# AD5940PSTAT.net
KiCad netlist of a schematic drawn in Altium Designer
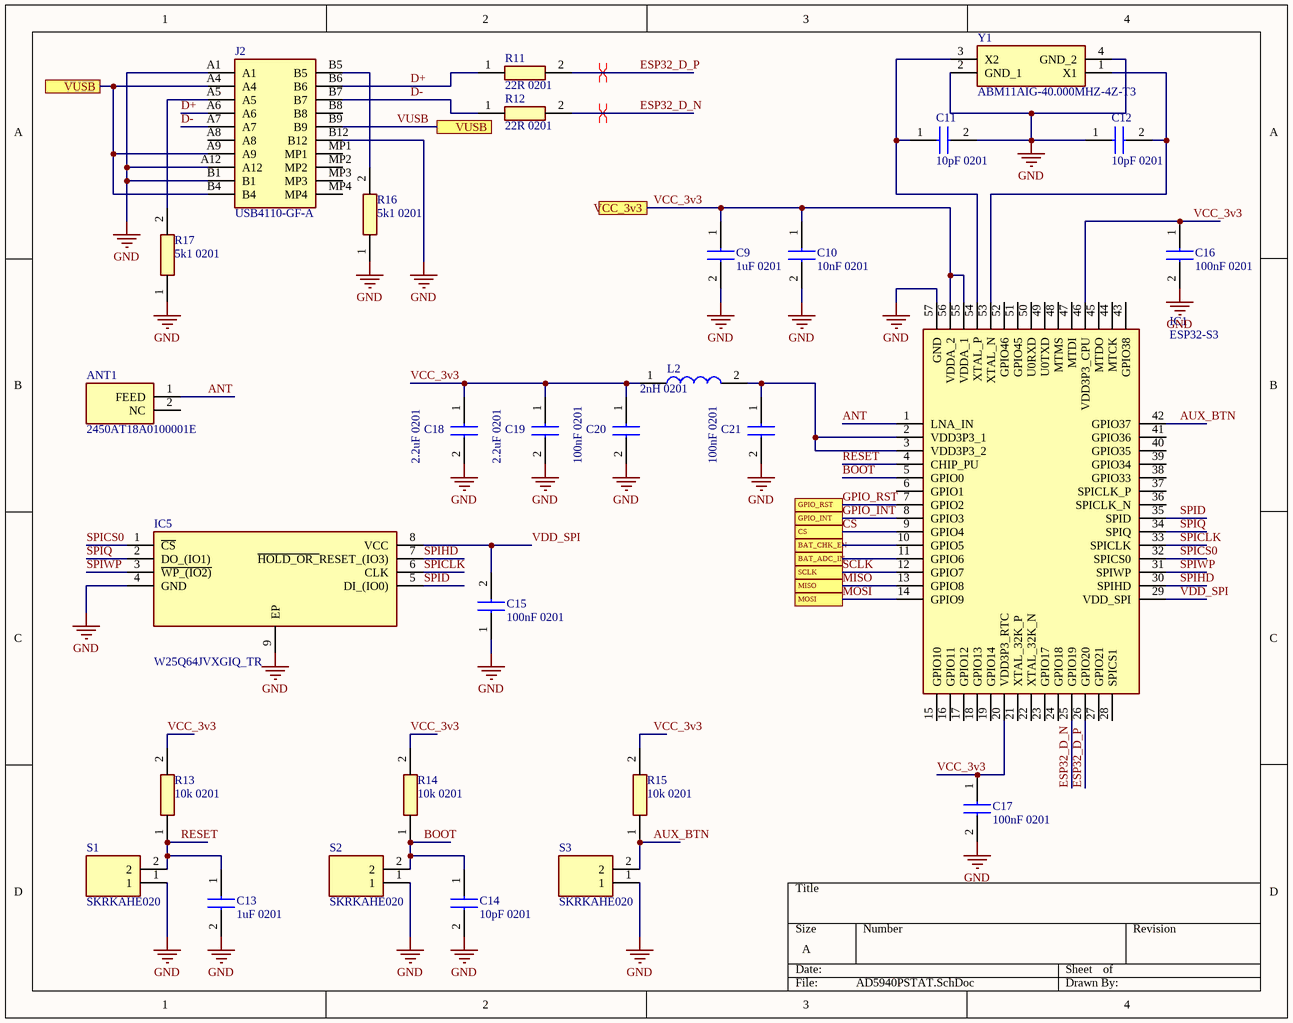
[diagram p0: AD5940PSTAT.SchDoc]

(export (version "E")
  (design (tool "Eeschema 10.0.6"))
  (components
    (comp (ref "ANT1")
      (value "2450AT18A0100001E")
      (footprint "SamacSys:2450AT18A0100001E")
      (description "Antenna")
      (libsource (lib "*") (part "2450AT18A0100001E"))
    )
    (comp (ref "C9")
      (value "1uF 0201")
      (footprint "SamacSys:CAPC0603X33N")
      (description "Capacitor")
      (fields
        (field (name "MANUFACTURER_PART_NUMBER") "02013A0R5BAT2A")
        (field (name "MOUSER PART NUMBER") "581-02013A0R5BAT2A")
      )
      (libsource (lib "*") (part "02013A0R5BAT2A"))
    )
    (comp (ref "C10")
      (value "10nF 0201")
      (footprint "SamacSys:CAPC0603X33N")
      (description "Capacitor")
      (fields
        (field (name "MANUFACTURER_PART_NUMBER") "02013A0R5BAT2A")
        (field (name "MOUSER PART NUMBER") "581-02013A0R5BAT2A")
      )
      (libsource (lib "*") (part "02013A0R5BAT2A"))
    )
    (comp (ref "C11")
      (value "10pF 0201")
      (footprint "SamacSys:CAPC0603X33N")
      (description "Capacitor")
      (fields
        (field (name "MANUFACTURER_PART_NUMBER") "02013A0R5BAT2A")
        (field (name "MOUSER PART NUMBER") "581-02013A0R5BAT2A")
      )
      (libsource (lib "*") (part "02013A0R5BAT2A"))
    )
    (comp (ref "C12")
      (value "10pF 0201")
      (footprint "SamacSys:CAPC0603X33N")
      (description "Capacitor")
      (fields
        (field (name "MANUFACTURER_PART_NUMBER") "02013A0R5BAT2A")
        (field (name "MOUSER PART NUMBER") "581-02013A0R5BAT2A")
      )
      (libsource (lib "*") (part "02013A0R5BAT2A"))
    )
    (comp (ref "C13")
      (value "1uF 0201")
      (footprint "SamacSys:CAPC0603X33N")
      (description "Capacitor")
      (fields
        (field (name "MANUFACTURER_PART_NUMBER") "02013A0R5BAT2A")
        (field (name "MOUSER PART NUMBER") "581-02013A0R5BAT2A")
      )
      (libsource (lib "*") (part "02013A0R5BAT2A"))
    )
    (comp (ref "C14")
      (value "10pF 0201")
      (footprint "SamacSys:CAPC0603X33N")
      (description "Capacitor")
      (fields
        (field (name "MANUFACTURER_PART_NUMBER") "02013A0R5BAT2A")
        (field (name "MOUSER PART NUMBER") "581-02013A0R5BAT2A")
      )
      (libsource (lib "*") (part "02013A0R5BAT2A"))
    )
    (comp (ref "C15")
      (value "100nF 0201")
      (footprint "SamacSys:CAPC0603X33N")
      (description "Capacitor")
      (fields
        (field (name "MANUFACTURER_PART_NUMBER") "02013A0R5BAT2A")
        (field (name "MOUSER PART NUMBER") "581-02013A0R5BAT2A")
      )
      (libsource (lib "*") (part "02013A0R5BAT2A"))
    )
    (comp (ref "C16")
      (value "100nF 0201")
      (footprint "SamacSys:CAPC0603X33N")
      (description "Capacitor")
      (fields
        (field (name "MANUFACTURER_PART_NUMBER") "02013A0R5BAT2A")
        (field (name "MOUSER PART NUMBER") "581-02013A0R5BAT2A")
      )
      (libsource (lib "*") (part "02013A0R5BAT2A"))
    )
    (comp (ref "C17")
      (value "100nF 0201")
      (footprint "SamacSys:CAPC0603X33N")
      (description "Capacitor")
      (fields
        (field (name "MANUFACTURER_PART_NUMBER") "02013A0R5BAT2A")
        (field (name "MOUSER PART NUMBER") "581-02013A0R5BAT2A")
      )
      (libsource (lib "*") (part "02013A0R5BAT2A"))
    )
    (comp (ref "C18")
      (value "2.2uF 0201")
      (footprint "SamacSys:CAPC0603X33N")
      (description "Capacitor")
      (fields
        (field (name "MANUFACTURER_PART_NUMBER") "02013A0R5BAT2A")
        (field (name "MOUSER PART NUMBER") "581-02013A0R5BAT2A")
      )
      (libsource (lib "*") (part "02013A0R5BAT2A"))
    )
    (comp (ref "C19")
      (value "2.2uF 0201")
      (footprint "SamacSys:CAPC0603X33N")
      (description "Capacitor")
      (fields
        (field (name "MANUFACTURER_PART_NUMBER") "02013A0R5BAT2A")
        (field (name "MOUSER PART NUMBER") "581-02013A0R5BAT2A")
      )
      (libsource (lib "*") (part "02013A0R5BAT2A"))
    )
    (comp (ref "C20")
      (value "100nF 0201")
      (footprint "SamacSys:CAPC0603X33N")
      (description "Capacitor")
      (fields
        (field (name "MANUFACTURER_PART_NUMBER") "02013A0R5BAT2A")
        (field (name "MOUSER PART NUMBER") "581-02013A0R5BAT2A")
      )
      (libsource (lib "*") (part "02013A0R5BAT2A"))
    )
    (comp (ref "C21")
      (value "100nF 0201")
      (footprint "SamacSys:CAPC0603X33N")
      (description "Capacitor")
      (fields
        (field (name "MANUFACTURER_PART_NUMBER") "02013A0R5BAT2A")
        (field (name "MOUSER PART NUMBER") "581-02013A0R5BAT2A")
      )
      (libsource (lib "*") (part "02013A0R5BAT2A"))
    )
    (comp (ref "IC1")
      (value "ESP32-S3")
      (footprint "SamacSys:QFN40P700X700X90-57N-D")
      (description "Integrated Circuit")
      (fields (field (name "MOUSER PART NUMBER") "356-ESP32-S3"))
      (libsource (lib "SamacSys") (part "ESP32-S3"))
    )
    (comp (ref "IC5")
      (value "W25Q64JVXGIQ_TR")
      (footprint "SamacSys:SON80P400X400X50-9N")
      (description "Integrated Circuit")
      (fields
        (field (name "MANUFACTURER_PART_NUMBER") "W25Q64JVXGIQ TR")
        (field (name "MOUSER PART NUMBER") "454-W25Q64JVXGIQTR")
      )
      (libsource (lib "*") (part "W25Q64JVXGIQ_TR"))
    )
    (comp (ref "J2")
      (value "USB4110-GF-A")
      (footprint "SamacSys:USB4110GFA")
      (description "Connector")
      (fields (field (name "MOUSER PART NUMBER") "640-USB4110-GF-A"))
      (libsource (lib "*") (part "USB4110-GF-A"))
    )
    (comp (ref "L2")
      (value "2nH 0201")
      (footprint "SamacSys:LQP03TG3N1B02D")
      (description "Inductor")
      (fields
        (field (name "MANUFACTURER_PART_NUMBER") "LQP03TN2N0C02D")
        (field (name "MOUSER PART NUMBER") "81-LQP03TN2N0C02D")
      )
      (libsource (lib "*") (part "LQP03TN2N0C02D"))
    )
    (comp (ref "R11")
      (value "22R 0201")
      (footprint "SamacSys:RESC0603X28N")
      (description "Resistor")
      (fields (field (name "MANUFACTURER_PART_NUMBER") "CPF0201D422RE1"))
      (libsource (lib "") (part "CPF0201D422RE1_1"))
    )
    (comp (ref "R12")
      (value "22R 0201")
      (footprint "SamacSys:RESC0603X28N")
      (description "Resistor")
      (fields (field (name "MANUFACTURER_PART_NUMBER") "CPF0201D422RE1"))
      (libsource (lib "") (part "CPF0201D422RE1_1"))
    )
    (comp (ref "R13")
      (value "10k 0201")
      (footprint "SamacSys:RESC0603X28N")
      (description "Resistor")
      (fields (field (name "MANUFACTURER_PART_NUMBER") "CPF0201D422RE1"))
      (libsource (lib "*") (part "CPF0201D422RE1"))
    )
    (comp (ref "R14")
      (value "10k 0201")
      (footprint "SamacSys:RESC0603X28N")
      (description "Resistor")
      (fields (field (name "MANUFACTURER_PART_NUMBER") "CPF0201D422RE1"))
      (libsource (lib "*") (part "CPF0201D422RE1"))
    )
    (comp (ref "R15")
      (value "10k 0201")
      (footprint "SamacSys:RESC0603X28N")
      (description "Resistor")
      (fields (field (name "MANUFACTURER_PART_NUMBER") "CPF0201D422RE1"))
      (libsource (lib "*") (part "CPF0201D422RE1"))
    )
    (comp (ref "R16")
      (value "5k1 0201")
      (footprint "SamacSys:RESC0603X28N")
      (description "Resistor")
      (fields (field (name "MANUFACTURER_PART_NUMBER") "CPF0201D422RE1"))
      (libsource (lib "*") (part "CPF0201D422RE1"))
    )
    (comp (ref "R17")
      (value "5k1 0201")
      (footprint "SamacSys:RESC0603X28N")
      (description "Resistor")
      (fields (field (name "MANUFACTURER_PART_NUMBER") "CPF0201D422RE1"))
      (libsource (lib "*") (part "CPF0201D422RE1"))
    )
    (comp (ref "S1")
      (value "SKRKAHE020")
      (footprint "SamacSys:SKRKAEE020")
      (description "Switch")
      (fields (field (name "MOUSER PART NUMBER") "688-SKRKAHE010"))
      (libsource (lib "*") (part "SKRKAHE020"))
    )
    (comp (ref "S2")
      (value "SKRKAHE020")
      (footprint "SamacSys:SKRKAEE020")
      (description "Switch")
      (fields (field (name "MOUSER PART NUMBER") "688-SKRKAHE010"))
      (libsource (lib "*") (part "SKRKAHE020"))
    )
    (comp (ref "S3")
      (value "SKRKAHE020")
      (footprint "SamacSys:SKRKAEE020")
      (description "Switch")
      (fields (field (name "MOUSER PART NUMBER") "688-SKRKAHE010"))
      (libsource (lib "*") (part "SKRKAHE020"))
    )
    (comp (ref "Y1")
      (value "ABM11AIG-40.000MHZ-4Z-T3")
      (footprint "SamacSys:ABM11AIG16000MHZ81ZT")
      (description "Crystal or Oscillator")
      (fields (field (name "MOUSER PART NUMBER") "815-M11AIG-40-4ZT3"))
      (libsource (lib "*") (part "ABM11AIG-40.000MHZ-4Z-T3"))
    )
  )
  (nets
    (net (code "1") (name "/ANT") (class "Default")
      (node (ref "ANT1") (pin "1") (pinfunction "FEED_1") (pintype "passive"))
      (node (ref "IC1") (pin "1") (pinfunction "LNA_IN_1") (pintype "passive"))
    )
    (net (code "2") (name "/AUX_BTN") (class "Default")
      (node (ref "IC1") (pin "42") (pinfunction "GPIO37_42") (pintype "passive"))
      (node (ref "R15") (pin "1") (pinfunction "1_1") (pintype "passive"))
      (node (ref "S3") (pin "2") (pinfunction "2_2") (pintype "passive"))
    )
    (net (code "3") (name "/BAT_ADC_IN") (class "Default")
      (node (ref "IC1") (pin "11") (pinfunction "GPIO6_11") (pintype "passive"))
    )
    (net (code "4") (name "/BAT_CHK_EN") (class "Default")
      (node (ref "IC1") (pin "10") (pinfunction "GPIO5_10") (pintype "passive"))
    )
    (net (code "5") (name "/BOOT") (class "Default")
      (node (ref "C14") (pin "1") (pinfunction "1_1") (pintype "passive"))
      (node (ref "IC1") (pin "5") (pinfunction "GPIO0_5") (pintype "passive"))
      (node (ref "R14") (pin "1") (pinfunction "1_1") (pintype "passive"))
      (node (ref "S2") (pin "2") (pinfunction "2_2") (pintype "passive"))
    )
    (net (code "6") (name "/CS") (class "Default")
      (node (ref "IC1") (pin "9") (pinfunction "GPIO4_9") (pintype "passive"))
    )
    (net (code "7") (name "/D+") (class "Default")
      (node (ref "J2") (pin "A6") (pinfunction "A6_A6") (pintype "passive"))
      (node (ref "J2") (pin "B6") (pinfunction "B6_B6") (pintype "passive"))
      (node (ref "R11") (pin "1") (pinfunction "1_1") (pintype "passive"))
    )
    (net (code "8") (name "/D-") (class "Default")
      (node (ref "J2") (pin "A7") (pinfunction "A7_A7") (pintype "passive"))
      (node (ref "J2") (pin "B7") (pinfunction "B7_B7") (pintype "passive"))
      (node (ref "R12") (pin "1") (pinfunction "1_1") (pintype "passive"))
    )
    (net (code "9") (name "/ESP32_D_N") (class "Default")
      (node (ref "IC1") (pin "25") (pinfunction "GPIO19_25") (pintype "passive"))
      (node (ref "R12") (pin "2") (pinfunction "2_2") (pintype "passive"))
    )
    (net (code "10") (name "/ESP32_D_P") (class "Default")
      (node (ref "IC1") (pin "26") (pinfunction "GPIO20_26") (pintype "passive"))
      (node (ref "R11") (pin "2") (pinfunction "2_2") (pintype "passive"))
    )
    (net (code "11") (name "/GPIO_INT") (class "Default")
      (node (ref "IC1") (pin "8") (pinfunction "GPIO3_8") (pintype "passive"))
    )
    (net (code "12") (name "/GPIO_RST") (class "Default")
      (node (ref "IC1") (pin "7") (pinfunction "GPIO2_7") (pintype "passive"))
    )
    (net (code "13") (name "/MISO") (class "Default")
      (node (ref "IC1") (pin "13") (pinfunction "GPIO8_13") (pintype "passive"))
    )
    (net (code "14") (name "/MOSI") (class "Default")
      (node (ref "IC1") (pin "14") (pinfunction "GPIO9_14") (pintype "passive"))
    )
    (net (code "15") (name "/RESET") (class "Default")
      (node (ref "C13") (pin "1") (pinfunction "1_1") (pintype "passive"))
      (node (ref "IC1") (pin "4") (pinfunction "CHIP_PU_4") (pintype "passive"))
      (node (ref "R13") (pin "1") (pinfunction "1_1") (pintype "passive"))
      (node (ref "S1") (pin "2") (pinfunction "2_2") (pintype "passive"))
    )
    (net (code "16") (name "/SCLK") (class "Default")
      (node (ref "IC1") (pin "12") (pinfunction "GPIO7_12") (pintype "passive"))
    )
    (net (code "17") (name "/SPICLK") (class "Default")
      (node (ref "IC1") (pin "33") (pinfunction "SPICLK_33") (pintype "passive"))
      (node (ref "IC5") (pin "6") (pinfunction "CLK_6") (pintype "passive"))
    )
    (net (code "18") (name "/SPICS0") (class "Default")
      (node (ref "IC1") (pin "32") (pinfunction "SPICS0_32") (pintype "passive"))
      (node (ref "IC5") (pin "1") (pinfunction "~{CS}_1") (pintype "passive"))
    )
    (net (code "19") (name "/SPID") (class "Default")
      (node (ref "IC1") (pin "35") (pinfunction "SPID_35") (pintype "passive"))
      (node (ref "IC5") (pin "5") (pinfunction "DI_(IO0)_5") (pintype "passive"))
    )
    (net (code "20") (name "/SPIHD") (class "Default")
      (node (ref "IC1") (pin "30") (pinfunction "SPIHD_30") (pintype "passive"))
      (node (ref "IC5") (pin "7") (pinfunction "~{HOLD_OR_}RESET_(IO3)_7") (pintype "passive"))
    )
    (net (code "21") (name "/SPIQ") (class "Default")
      (node (ref "IC1") (pin "34") (pinfunction "SPIQ_34") (pintype "passive"))
      (node (ref "IC5") (pin "2") (pinfunction "DO_(IO1)_2") (pintype "passive"))
    )
    (net (code "22") (name "/SPIWP") (class "Default")
      (node (ref "IC1") (pin "31") (pinfunction "SPIWP_31") (pintype "passive"))
      (node (ref "IC5") (pin "3") (pinfunction "~{WP_(IO2)}_3") (pintype "passive"))
    )
    (net (code "23") (name "/VCC_3v3") (class "Default")
      (node (ref "C10") (pin "1") (pinfunction "1_1") (pintype "passive"))
      (node (ref "C16") (pin "1") (pinfunction "1_1") (pintype "passive"))
      (node (ref "C17") (pin "1") (pinfunction "1_1") (pintype "passive"))
      (node (ref "C18") (pin "1") (pinfunction "1_1") (pintype "passive"))
      (node (ref "C19") (pin "1") (pinfunction "1_1") (pintype "passive"))
      (node (ref "C20") (pin "1") (pinfunction "1_1") (pintype "passive"))
      (node (ref "C9") (pin "1") (pinfunction "1_1") (pintype "passive"))
      (node (ref "IC1") (pin "20") (pinfunction "VDD3P3_RTC_20") (pintype "passive"))
      (node (ref "IC1") (pin "46") (pinfunction "VDD3P3_CPU_46") (pintype "passive"))
      (node (ref "IC1") (pin "55") (pinfunction "VDDA_1_55") (pintype "passive"))
      (node (ref "IC1") (pin "56") (pinfunction "VDDA_2_56") (pintype "passive"))
      (node (ref "L2") (pin "1") (pinfunction "1_1") (pintype "passive"))
      (node (ref "R13") (pin "2") (pinfunction "2_2") (pintype "passive"))
      (node (ref "R14") (pin "2") (pinfunction "2_2") (pintype "passive"))
      (node (ref "R15") (pin "2") (pinfunction "2_2") (pintype "passive"))
    )
    (net (code "24") (name "/VDD_SPI") (class "Default")
      (node (ref "C15") (pin "2") (pinfunction "2_2") (pintype "passive"))
      (node (ref "IC1") (pin "29") (pinfunction "VDD_SPI_29") (pintype "passive"))
      (node (ref "IC5") (pin "8") (pinfunction "VCC_8") (pintype "passive"))
    )
    (net (code "25") (name "/VUSB") (class "Default")
      (node (ref "J2") (pin "A4") (pinfunction "A4_A4") (pintype "passive"))
      (node (ref "J2") (pin "A9") (pinfunction "A9_A9") (pintype "passive"))
      (node (ref "J2") (pin "B4") (pinfunction "B4_B4") (pintype "passive"))
      (node (ref "J2") (pin "B9") (pinfunction "B9_B9") (pintype "passive"))
    )
    (net (code "26") (name "GND") (class "Default")
      (node (ref "C10") (pin "2") (pinfunction "2_2") (pintype "passive"))
      (node (ref "C11") (pin "2") (pinfunction "2_2") (pintype "passive"))
      (node (ref "C12") (pin "1") (pinfunction "1_1") (pintype "passive"))
      (node (ref "C13") (pin "2") (pinfunction "2_2") (pintype "passive"))
      (node (ref "C14") (pin "2") (pinfunction "2_2") (pintype "passive"))
      (node (ref "C15") (pin "1") (pinfunction "1_1") (pintype "passive"))
      (node (ref "C16") (pin "2") (pinfunction "2_2") (pintype "passive"))
      (node (ref "C17") (pin "2") (pinfunction "2_2") (pintype "passive"))
      (node (ref "C18") (pin "2") (pinfunction "2_2") (pintype "passive"))
      (node (ref "C19") (pin "2") (pinfunction "2_2") (pintype "passive"))
      (node (ref "C20") (pin "2") (pinfunction "2_2") (pintype "passive"))
      (node (ref "C21") (pin "2") (pinfunction "2_2") (pintype "passive"))
      (node (ref "C9") (pin "2") (pinfunction "2_2") (pintype "passive"))
      (node (ref "IC1") (pin "57") (pinfunction "GND_57") (pintype "passive"))
      (node (ref "IC5") (pin "4") (pinfunction "GND_4") (pintype "passive"))
      (node (ref "IC5") (pin "9") (pinfunction "EP_9") (pintype "passive"))
      (node (ref "J2") (pin "A1") (pinfunction "A1_A1") (pintype "passive"))
      (node (ref "J2") (pin "A12") (pinfunction "A12_A12") (pintype "passive"))
      (node (ref "J2") (pin "B1") (pinfunction "B1_B1") (pintype "passive"))
      (node (ref "J2") (pin "B12") (pinfunction "B12_B12") (pintype "passive"))
      (node (ref "R16") (pin "1") (pinfunction "1_1") (pintype "passive"))
      (node (ref "R17") (pin "1") (pinfunction "1_1") (pintype "passive"))
      (node (ref "S1") (pin "1") (pinfunction "1_1") (pintype "passive"))
      (node (ref "S2") (pin "1") (pinfunction "1_1") (pintype "passive"))
      (node (ref "S3") (pin "1") (pinfunction "1_1") (pintype "passive"))
      (node (ref "Y1") (pin "2") (pinfunction "GND_1_2") (pintype "passive"))
      (node (ref "Y1") (pin "4") (pinfunction "GND_2_4") (pintype "passive"))
    )
    (net (code "27") (name "Net-(IC1-VDD3P3_1)") (class "Default")
      (node (ref "C21") (pin "1") (pinfunction "1_1") (pintype "passive"))
      (node (ref "IC1") (pin "2") (pinfunction "VDD3P3_1_2") (pintype "passive"))
      (node (ref "IC1") (pin "3") (pinfunction "VDD3P3_2_3") (pintype "passive"))
      (node (ref "L2") (pin "2") (pinfunction "2_2") (pintype "passive"))
    )
    (net (code "28") (name "Net-(IC1-XTAL_N)") (class "Default")
      (node (ref "C12") (pin "2") (pinfunction "2_2") (pintype "passive"))
      (node (ref "IC1") (pin "53") (pinfunction "XTAL_N_53") (pintype "passive"))
      (node (ref "Y1") (pin "1") (pinfunction "X1_1") (pintype "passive"))
    )
    (net (code "29") (name "Net-(IC1-XTAL_P)") (class "Default")
      (node (ref "C11") (pin "1") (pinfunction "1_1") (pintype "passive"))
      (node (ref "IC1") (pin "54") (pinfunction "XTAL_P_54") (pintype "passive"))
      (node (ref "Y1") (pin "3") (pinfunction "X2_3") (pintype "passive"))
    )
    (net (code "30") (name "Net-(J2-PadA5)") (class "Default")
      (node (ref "J2") (pin "A5") (pinfunction "A5_A5") (pintype "passive"))
      (node (ref "R17") (pin "2") (pinfunction "2_2") (pintype "passive"))
    )
    (net (code "31") (name "Net-(J2-PadB5)") (class "Default")
      (node (ref "J2") (pin "B5") (pinfunction "B5_B5") (pintype "passive"))
      (node (ref "R16") (pin "2") (pinfunction "2_2") (pintype "passive"))
    )
    (net (code "32") (name "unconnected-(ANT1-NC-Pad2)") (class "Default")
      (node (ref "ANT1") (pin "2") (pinfunction "NC_2") (pintype "passive"))
    )
    (net (code "33") (name "unconnected-(IC1-GPIO1-Pad6)") (class "Default")
      (node (ref "IC1") (pin "6") (pinfunction "GPIO1_6") (pintype "passive"))
    )
    (net (code "34") (name "unconnected-(IC1-GPIO10-Pad15)") (class "Default")
      (node (ref "IC1") (pin "15") (pinfunction "GPIO10_15") (pintype "passive"))
    )
    (net (code "35") (name "unconnected-(IC1-GPIO11-Pad16)") (class "Default")
      (node (ref "IC1") (pin "16") (pinfunction "GPIO11_16") (pintype "passive"))
    )
    (net (code "36") (name "unconnected-(IC1-GPIO12-Pad17)") (class "Default")
      (node (ref "IC1") (pin "17") (pinfunction "GPIO12_17") (pintype "passive"))
    )
    (net (code "37") (name "unconnected-(IC1-GPIO13-Pad18)") (class "Default")
      (node (ref "IC1") (pin "18") (pinfunction "GPIO13_18") (pintype "passive"))
    )
    (net (code "38") (name "unconnected-(IC1-GPIO14-Pad19)") (class "Default")
      (node (ref "IC1") (pin "19") (pinfunction "GPIO14_19") (pintype "passive"))
    )
    (net (code "39") (name "unconnected-(IC1-GPIO17-Pad23)") (class "Default")
      (node (ref "IC1") (pin "23") (pinfunction "GPIO17_23") (pintype "passive"))
    )
    (net (code "40") (name "unconnected-(IC1-GPIO18-Pad24)") (class "Default")
      (node (ref "IC1") (pin "24") (pinfunction "GPIO18_24") (pintype "passive"))
    )
    (net (code "41") (name "unconnected-(IC1-GPIO21-Pad27)") (class "Default")
      (node (ref "IC1") (pin "27") (pinfunction "GPIO21_27") (pintype "passive"))
    )
    (net (code "42") (name "unconnected-(IC1-GPIO33-Pad38)") (class "Default")
      (node (ref "IC1") (pin "38") (pinfunction "GPIO33_38") (pintype "passive"))
    )
    (net (code "43") (name "unconnected-(IC1-GPIO34-Pad39)") (class "Default")
      (node (ref "IC1") (pin "39") (pinfunction "GPIO34_39") (pintype "passive"))
    )
    (net (code "44") (name "unconnected-(IC1-GPIO35-Pad40)") (class "Default")
      (node (ref "IC1") (pin "40") (pinfunction "GPIO35_40") (pintype "passive"))
    )
    (net (code "45") (name "unconnected-(IC1-GPIO36-Pad41)") (class "Default")
      (node (ref "IC1") (pin "41") (pinfunction "GPIO36_41") (pintype "passive"))
    )
    (net (code "46") (name "unconnected-(IC1-GPIO38-Pad43)") (class "Default")
      (node (ref "IC1") (pin "43") (pinfunction "GPIO38_43") (pintype "passive"))
    )
    (net (code "47") (name "unconnected-(IC1-GPIO45-Pad51)") (class "Default")
      (node (ref "IC1") (pin "51") (pinfunction "GPIO45_51") (pintype "passive"))
    )
    (net (code "48") (name "unconnected-(IC1-GPIO46-Pad52)") (class "Default")
      (node (ref "IC1") (pin "52") (pinfunction "GPIO46_52") (pintype "passive"))
    )
    (net (code "49") (name "unconnected-(IC1-MTCK-Pad44)") (class "Default")
      (node (ref "IC1") (pin "44") (pinfunction "MTCK_44") (pintype "passive"))
    )
    (net (code "50") (name "unconnected-(IC1-MTDI-Pad47)") (class "Default")
      (node (ref "IC1") (pin "47") (pinfunction "MTDI_47") (pintype "passive"))
    )
    (net (code "51") (name "unconnected-(IC1-MTDO-Pad45)") (class "Default")
      (node (ref "IC1") (pin "45") (pinfunction "MTDO_45") (pintype "passive"))
    )
    (net (code "52") (name "unconnected-(IC1-MTMS-Pad48)") (class "Default")
      (node (ref "IC1") (pin "48") (pinfunction "MTMS_48") (pintype "passive"))
    )
    (net (code "53") (name "unconnected-(IC1-SPICLK_N-Pad36)") (class "Default")
      (node (ref "IC1") (pin "36") (pinfunction "SPICLK_N_36") (pintype "passive"))
    )
    (net (code "54") (name "unconnected-(IC1-SPICLK_P-Pad37)") (class "Default")
      (node (ref "IC1") (pin "37") (pinfunction "SPICLK_P_37") (pintype "passive"))
    )
    (net (code "55") (name "unconnected-(IC1-SPICS1-Pad28)") (class "Default")
      (node (ref "IC1") (pin "28") (pinfunction "SPICS1_28") (pintype "passive"))
    )
    (net (code "56") (name "unconnected-(IC1-U0RXD-Pad50)") (class "Default")
      (node (ref "IC1") (pin "50") (pinfunction "U0RXD_50") (pintype "passive"))
    )
    (net (code "57") (name "unconnected-(IC1-U0TXD-Pad49)") (class "Default")
      (node (ref "IC1") (pin "49") (pinfunction "U0TXD_49") (pintype "passive"))
    )
    (net (code "58") (name "unconnected-(IC1-XTAL_32K_N-Pad22)") (class "Default")
      (node (ref "IC1") (pin "22") (pinfunction "XTAL_32K_N_22") (pintype "passive"))
    )
    (net (code "59") (name "unconnected-(IC1-XTAL_32K_P-Pad21)") (class "Default")
      (node (ref "IC1") (pin "21") (pinfunction "XTAL_32K_P_21") (pintype "passive"))
    )
    (net (code "60") (name "unconnected-(J2-PadA8)") (class "Default")
      (node (ref "J2") (pin "A8") (pinfunction "A8_A8") (pintype "passive"))
    )
    (net (code "61") (name "unconnected-(J2-PadB8)") (class "Default")
      (node (ref "J2") (pin "B8") (pinfunction "B8_B8") (pintype "passive"))
    )
    (net (code "62") (name "unconnected-(J2-PadMP1)") (class "Default")
      (node (ref "J2") (pin "MP1") (pinfunction "MP1_MP1") (pintype "passive"))
    )
    (net (code "63") (name "unconnected-(J2-PadMP2)") (class "Default")
      (node (ref "J2") (pin "MP2") (pinfunction "MP2_MP2") (pintype "passive"))
    )
    (net (code "64") (name "unconnected-(J2-PadMP3)") (class "Default")
      (node (ref "J2") (pin "MP3") (pinfunction "MP3_MP3") (pintype "passive"))
    )
    (net (code "65") (name "unconnected-(J2-PadMP4)") (class "Default")
      (node (ref "J2") (pin "MP4") (pinfunction "MP4_MP4") (pintype "passive"))
    )
  )
)
